# VCLFO_th.net
KiCad netlist of a schematic drawn in EAGLE
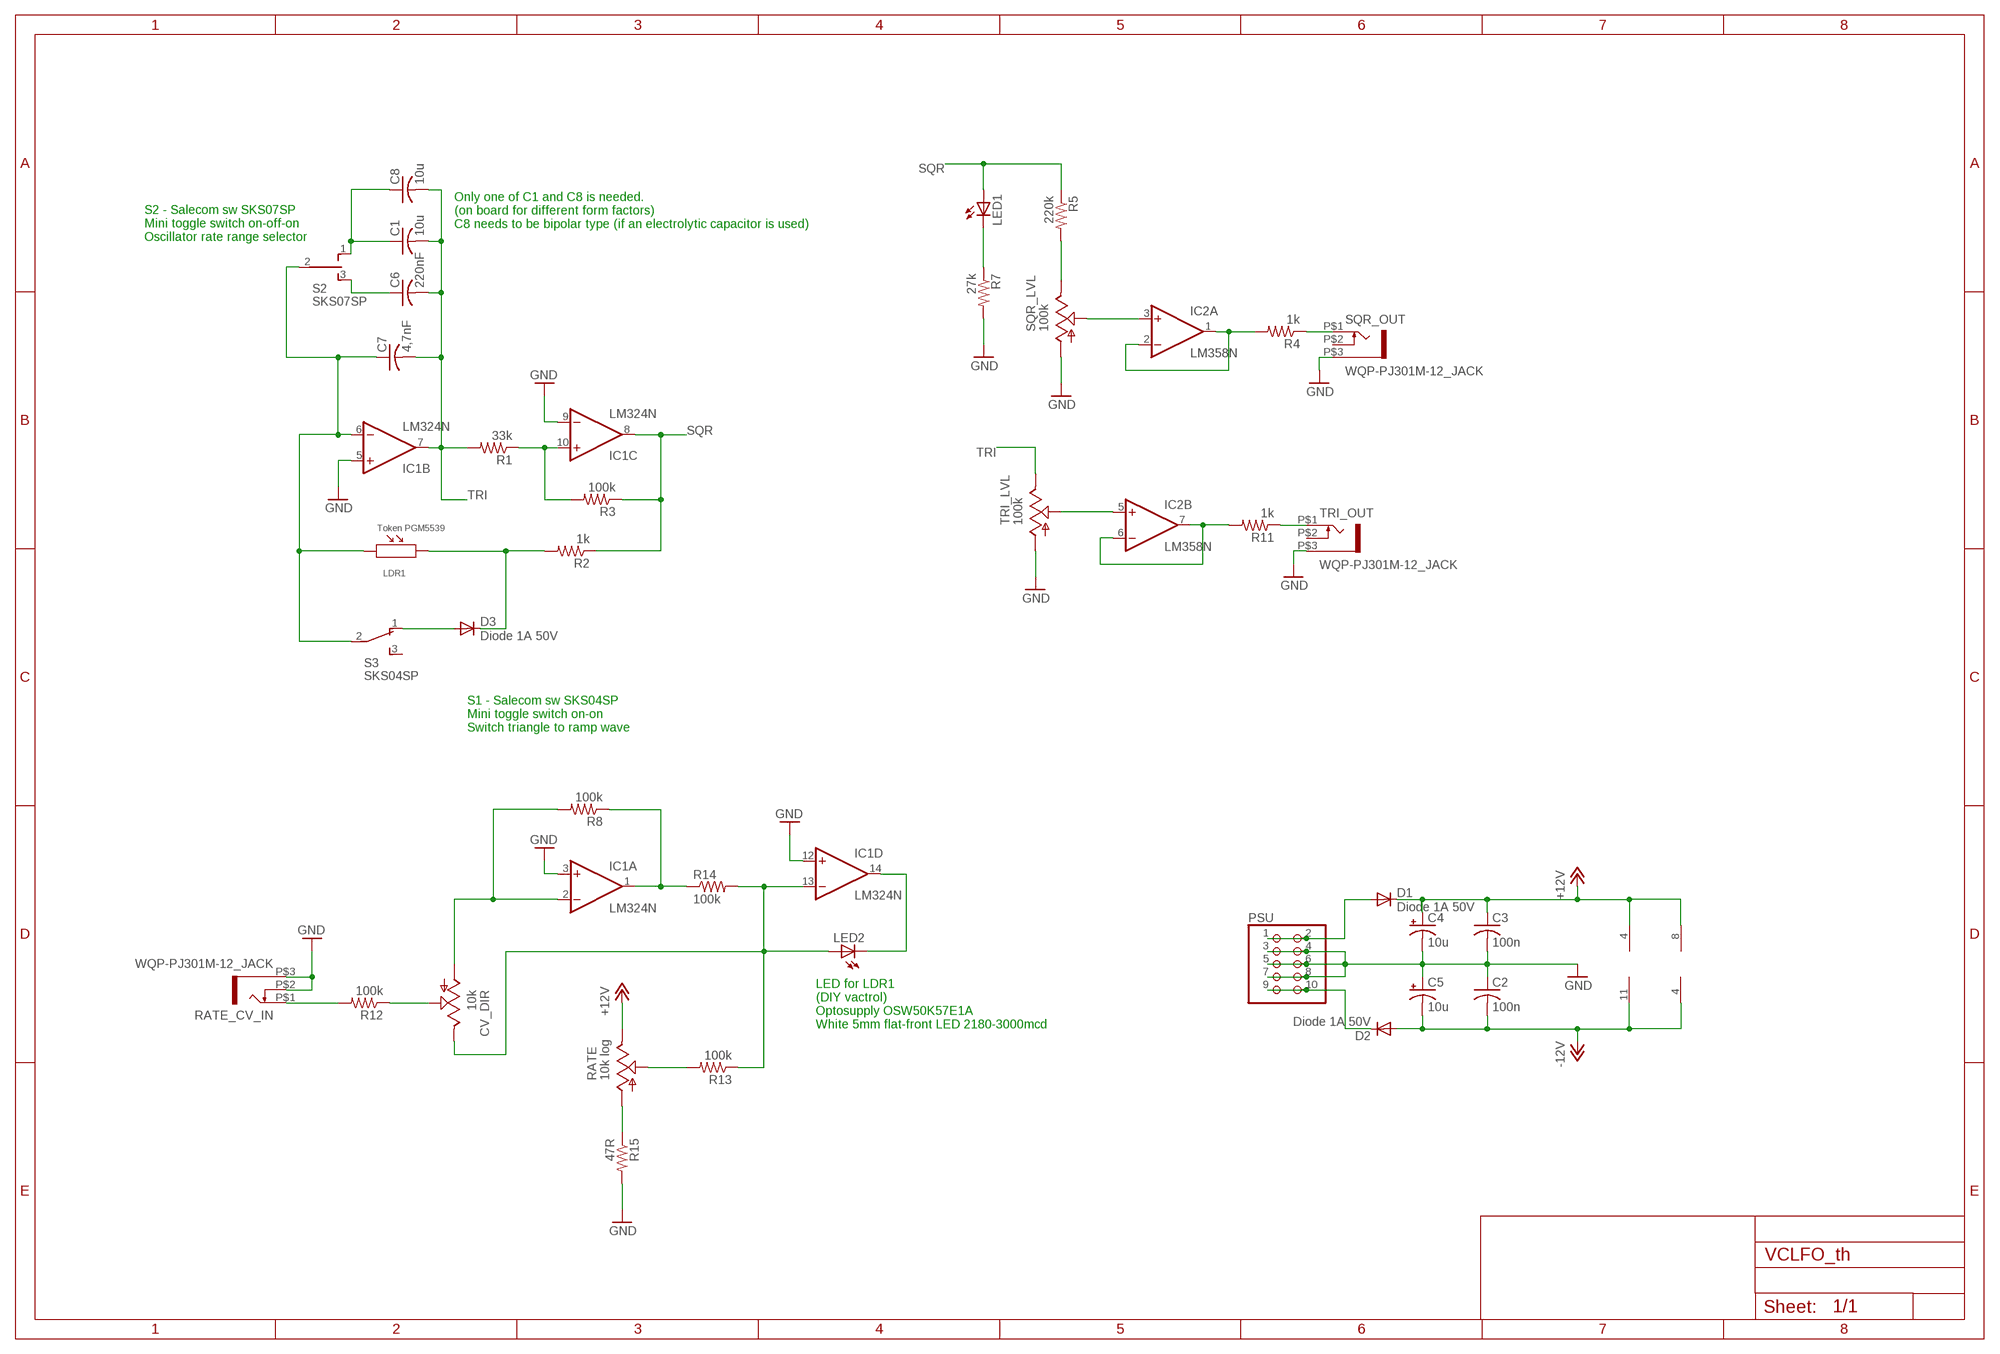
[diagram p0: schematic, sheet 1]

(export (version "E")
  (design (tool "Eeschema 10.0.6"))
  (components
    (comp (ref "C1")
      (value "10u")
      (footprint "eagle-import:C1206")
      (libsource (lib "eagle-import") (part "C-USC1206"))
    )
    (comp (ref "C2")
      (value "100n")
      (footprint "eagle-import:C025-025X050")
      (libsource (lib "eagle-import") (part "C-US025-025X050"))
    )
    (comp (ref "C3")
      (value "100n")
      (footprint "eagle-import:C025-025X050")
      (libsource (lib "eagle-import") (part "C-US025-025X050"))
    )
    (comp (ref "C4")
      (value "10u")
      (footprint "eagle-import:E2,5-6")
      (libsource (lib "eagle-import") (part "CPOL-USE2.5-6"))
    )
    (comp (ref "C5")
      (value "10u")
      (footprint "eagle-import:E2,5-6")
      (libsource (lib "eagle-import") (part "CPOL-USE2.5-6"))
    )
    (comp (ref "C6")
      (value "220nF")
      (footprint "eagle-import:C025-025X050")
      (libsource (lib "eagle-import") (part "C-US025-025X050"))
    )
    (comp (ref "C7")
      (value "4,7nF")
      (footprint "eagle-import:C025-025X050")
      (libsource (lib "eagle-import") (part "C-US025-025X050"))
    )
    (comp (ref "C8")
      (value "10u")
      (footprint "eagle-import:C025-050X050")
      (libsource (lib "eagle-import") (part "C-US025-050X050"))
    )
    (comp (ref "CV_DIR")
      (value "10k")
      (footprint "eagle-import:ALPS_POT_VERTICAL")
      (libsource (lib "eagle-import") (part "POT_USVERTICAL"))
    )
    (comp (ref "D1")
      (value "Diode 1A 50V")
      (footprint "eagle-import:D-5")
      (libsource (lib "eagle-import") (part "DIODE-D-5"))
    )
    (comp (ref "D2")
      (value "Diode 1A 50V")
      (footprint "eagle-import:D-5")
      (libsource (lib "eagle-import") (part "DIODE-D-5"))
    )
    (comp (ref "D3")
      (value "Diode 1A 50V")
      (footprint "eagle-import:D-5")
      (libsource (lib "eagle-import") (part "DIODE-D-5"))
    )
    (comp (ref "IC1")
      (value "LM324N")
      (footprint "eagle-import:DIL14")
      (libsource (lib "eagle-import") (part "LM324N"))
    )
    (comp (ref "IC2")
      (value "LM358N")
      (footprint "eagle-import:DIL08")
      (libsource (lib "eagle-import") (part "LM358N"))
    )
    (comp (ref "LDR1")
      (value "Token PGM5539")
      (footprint "eagle-import:LDR_SNR2-3.0")
      (fields (field (name "MPN") "PGM55xx"))
      (libsource (lib "eagle-import") (part "LDR_TOKEN_PGM55XX"))
    )
    (comp (ref "LED1")
      (value "LED5MM")
      (footprint "eagle-import:LED5MM")
      (libsource (lib "eagle-import") (part "LED5MM"))
    )
    (comp (ref "LED2")
      (value "LED3MM")
      (footprint "eagle-import:LED3MM")
      (libsource (lib "eagle-import") (part "LED3MM"))
    )
    (comp (ref "PSU")
      (value "PINHD-2X5")
      (footprint "eagle-import:2X05")
      (libsource (lib "eagle-import") (part "PINHD-2X5"))
    )
    (comp (ref "R1")
      (value "33k")
      (footprint "eagle-import:0207_2V")
      (libsource (lib "eagle-import") (part "R-US_0207/2V"))
    )
    (comp (ref "R2")
      (value "1k")
      (footprint "eagle-import:0207_2V")
      (libsource (lib "eagle-import") (part "R-US_0207/2V"))
    )
    (comp (ref "R3")
      (value "100k")
      (footprint "eagle-import:0207_2V")
      (libsource (lib "eagle-import") (part "R-US_0207/2V"))
    )
    (comp (ref "R4")
      (value "1k")
      (footprint "eagle-import:0207_2V")
      (libsource (lib "eagle-import") (part "R-US_0207/2V"))
    )
    (comp (ref "R5")
      (value "220k")
      (footprint "eagle-import:0207_2V")
      (libsource (lib "eagle-import") (part "R-US_0207/2V"))
    )
    (comp (ref "R7")
      (value "27k")
      (footprint "eagle-import:0207_2V")
      (libsource (lib "eagle-import") (part "R-US_0207/2V"))
    )
    (comp (ref "R8")
      (value "100k")
      (footprint "eagle-import:0207_2V")
      (libsource (lib "eagle-import") (part "R-US_0207/2V"))
    )
    (comp (ref "R11")
      (value "1k")
      (footprint "eagle-import:0207_2V")
      (libsource (lib "eagle-import") (part "R-US_0207/2V"))
    )
    (comp (ref "R12")
      (value "100k")
      (footprint "eagle-import:0207_2V")
      (libsource (lib "eagle-import") (part "R-US_0207/2V"))
    )
    (comp (ref "R13")
      (value "100k")
      (footprint "eagle-import:0207_2V")
      (libsource (lib "eagle-import") (part "R-US_0207/2V"))
    )
    (comp (ref "R14")
      (value "100k")
      (footprint "eagle-import:0207_2V")
      (libsource (lib "eagle-import") (part "R-US_0207/2V"))
    )
    (comp (ref "R15")
      (value "47R")
      (footprint "eagle-import:0207_2V")
      (libsource (lib "eagle-import") (part "R-US_0207/2V"))
    )
    (comp (ref "RATE")
      (value "10k log")
      (footprint "eagle-import:ALPS_POT_VERTICAL")
      (libsource (lib "eagle-import") (part "POT_USVERTICAL"))
    )
    (comp (ref "RATE_CV_IN")
      (value "WQP-PJ301M-12_JACK")
      (footprint "eagle-import:WQP-PJ301M-12_JACK")
      (libsource (lib "eagle-import") (part "WQP-PJ301M-12_JACK"))
    )
    (comp (ref "S2")
      (value "SKS07SP")
      (footprint "eagle-import:TL3XPO")
      (libsource (lib "eagle-import") (part "TL39PO"))
    )
    (comp (ref "S3")
      (value "SKS04SP")
      (footprint "eagle-import:TL3XPO")
      (libsource (lib "eagle-import") (part "TL36PO"))
    )
    (comp (ref "SQR_LVL")
      (value "100k")
      (footprint "eagle-import:ALPS_POT_VERTICAL")
      (libsource (lib "eagle-import") (part "POT_USVERTICAL"))
    )
    (comp (ref "SQR_OUT")
      (value "WQP-PJ301M-12_JACK")
      (footprint "eagle-import:WQP-PJ301M-12_JACK")
      (libsource (lib "eagle-import") (part "WQP-PJ301M-12_JACK"))
    )
    (comp (ref "TRI_LVL")
      (value "100k")
      (footprint "eagle-import:ALPS_POT_VERTICAL")
      (libsource (lib "eagle-import") (part "POT_USVERTICAL"))
    )
    (comp (ref "TRI_OUT")
      (value "WQP-PJ301M-12_JACK")
      (footprint "eagle-import:WQP-PJ301M-12_JACK")
      (libsource (lib "eagle-import") (part "WQP-PJ301M-12_JACK"))
    )
  )
  (nets
    (net (code "1") (name "+12V") (class "Default")
      (node (ref "C3") (pin "1") (pinfunction "1_1") (pintype "passive"))
      (node (ref "C4") (pin "+") (pinfunction "+_+") (pintype "passive"))
      (node (ref "D1") (pin "C") (pinfunction "C_C") (pintype "passive"))
      (node (ref "IC1") (pin "4") (pinfunction "V+_4") (pintype "power_in"))
      (node (ref "IC2") (pin "8") (pinfunction "V+_8") (pintype "power_in"))
      (node (ref "RATE") (pin "P$1") (pinfunction "E_P$1") (pintype "passive"))
    )
    (net (code "2") (name "-12V") (class "Default")
      (node (ref "C2") (pin "2") (pinfunction "2_2") (pintype "passive"))
      (node (ref "C5") (pin "-") (pinfunction "-_-") (pintype "passive"))
      (node (ref "D2") (pin "A") (pinfunction "A_A") (pintype "passive"))
      (node (ref "IC1") (pin "11") (pinfunction "V-_11") (pintype "power_in"))
      (node (ref "IC2") (pin "4") (pinfunction "V-_4") (pintype "power_in"))
    )
    (net (code "3") (name "/SQR") (class "Default")
      (node (ref "IC1") (pin "8") (pinfunction "OUT_8") (pintype "output"))
      (node (ref "LED1") (pin "A") (pinfunction "A_A") (pintype "passive"))
      (node (ref "R2") (pin "1") (pinfunction "1_1") (pintype "passive"))
      (node (ref "R3") (pin "1") (pinfunction "1_1") (pintype "passive"))
      (node (ref "R5") (pin "1") (pinfunction "1_1") (pintype "passive"))
    )
    (net (code "4") (name "/TRI") (class "Default")
      (node (ref "C1") (pin "2") (pinfunction "2_2") (pintype "passive"))
      (node (ref "C6") (pin "2") (pinfunction "2_2") (pintype "passive"))
      (node (ref "C7") (pin "2") (pinfunction "2_2") (pintype "passive"))
      (node (ref "C8") (pin "2") (pinfunction "2_2") (pintype "passive"))
      (node (ref "IC1") (pin "7") (pinfunction "OUT_7") (pintype "output"))
      (node (ref "R1") (pin "2") (pinfunction "2_2") (pintype "passive"))
      (node (ref "TRI_LVL") (pin "P$1") (pinfunction "E_P$1") (pintype "passive"))
    )
    (net (code "5") (name "GND") (class "Default")
      (node (ref "C2") (pin "1") (pinfunction "1_1") (pintype "passive"))
      (node (ref "C3") (pin "2") (pinfunction "2_2") (pintype "passive"))
      (node (ref "C4") (pin "-") (pinfunction "-_-") (pintype "passive"))
      (node (ref "C5") (pin "+") (pinfunction "+_+") (pintype "passive"))
      (node (ref "IC1") (pin "12") (pinfunction "+IN_12") (pintype "input"))
      (node (ref "IC1") (pin "3") (pinfunction "+IN_3") (pintype "input"))
      (node (ref "IC1") (pin "5") (pinfunction "+IN_5") (pintype "input"))
      (node (ref "IC1") (pin "9") (pinfunction "-IN_9") (pintype "input"))
      (node (ref "PSU") (pin "3") (pinfunction "3_3") (pintype "passive"))
      (node (ref "PSU") (pin "4") (pinfunction "4_4") (pintype "passive"))
      (node (ref "PSU") (pin "5") (pinfunction "5_5") (pintype "passive"))
      (node (ref "PSU") (pin "6") (pinfunction "6_6") (pintype "passive"))
      (node (ref "PSU") (pin "7") (pinfunction "7_7") (pintype "passive"))
      (node (ref "PSU") (pin "8") (pinfunction "8_8") (pintype "passive"))
      (node (ref "R15") (pin "2") (pinfunction "2_2") (pintype "passive"))
      (node (ref "R7") (pin "2") (pinfunction "2_2") (pintype "passive"))
      (node (ref "RATE_CV_IN") (pin "P$2") (pinfunction "3_P$2") (pintype "passive"))
      (node (ref "RATE_CV_IN") (pin "P$3") (pinfunction "1_P$3") (pintype "passive"))
      (node (ref "SQR_LVL") (pin "P$3") (pinfunction "A_P$3") (pintype "passive"))
      (node (ref "SQR_OUT") (pin "P$3") (pinfunction "1_P$3") (pintype "passive"))
      (node (ref "TRI_LVL") (pin "P$3") (pinfunction "A_P$3") (pintype "passive"))
      (node (ref "TRI_OUT") (pin "P$3") (pinfunction "1_P$3") (pintype "passive"))
    )
    (net (code "6") (name "Net-(CV_DIR-A)") (class "Default")
      (node (ref "CV_DIR") (pin "P$3") (pinfunction "A_P$3") (pintype "passive"))
      (node (ref "IC1") (pin "2") (pinfunction "-IN_2") (pintype "input"))
      (node (ref "R8") (pin "2") (pinfunction "2_2") (pintype "passive"))
    )
    (net (code "7") (name "Net-(CV_DIR-E)") (class "Default")
      (node (ref "CV_DIR") (pin "P$1") (pinfunction "E_P$1") (pintype "passive"))
      (node (ref "IC1") (pin "13") (pinfunction "-IN_13") (pintype "input"))
      (node (ref "LED2") (pin "A") (pinfunction "A_A") (pintype "passive"))
      (node (ref "R13") (pin "1") (pinfunction "1_1") (pintype "passive"))
      (node (ref "R14") (pin "2") (pinfunction "2_2") (pintype "passive"))
    )
    (net (code "8") (name "Net-(CV_DIR-S)") (class "Default")
      (node (ref "CV_DIR") (pin "P$2") (pinfunction "S_P$2") (pintype "passive"))
      (node (ref "R12") (pin "1") (pinfunction "1_1") (pintype "passive"))
    )
    (net (code "9") (name "Net-(D1-PadA)") (class "Default")
      (node (ref "D1") (pin "A") (pinfunction "A_A") (pintype "passive"))
      (node (ref "PSU") (pin "1") (pinfunction "1_1") (pintype "passive"))
      (node (ref "PSU") (pin "2") (pinfunction "2_2") (pintype "passive"))
    )
    (net (code "10") (name "Net-(D2-PadC)") (class "Default")
      (node (ref "D2") (pin "C") (pinfunction "C_C") (pintype "passive"))
      (node (ref "PSU") (pin "10") (pinfunction "10_10") (pintype "passive"))
      (node (ref "PSU") (pin "9") (pinfunction "9_9") (pintype "passive"))
    )
    (net (code "11") (name "Net-(IC1A-OUT)") (class "Default")
      (node (ref "IC1") (pin "1") (pinfunction "OUT_1") (pintype "output"))
      (node (ref "R14") (pin "1") (pinfunction "1_1") (pintype "passive"))
      (node (ref "R8") (pin "1") (pinfunction "1_1") (pintype "passive"))
    )
    (net (code "12") (name "Net-(IC1B--IN)") (class "Default")
      (node (ref "C7") (pin "1") (pinfunction "1_1") (pintype "passive"))
      (node (ref "IC1") (pin "6") (pinfunction "-IN_6") (pintype "input"))
      (node (ref "LDR1") (pin "1") (pinfunction "P$1_1") (pintype "bidirectional"))
      (node (ref "S2") (pin "2") (pinfunction "P_2") (pintype "passive"))
      (node (ref "S3") (pin "2") (pinfunction "P_2") (pintype "passive"))
    )
    (net (code "13") (name "Net-(IC1C-+IN)") (class "Default")
      (node (ref "IC1") (pin "10") (pinfunction "+IN_10") (pintype "input"))
      (node (ref "R1") (pin "1") (pinfunction "1_1") (pintype "passive"))
      (node (ref "R3") (pin "2") (pinfunction "2_2") (pintype "passive"))
    )
    (net (code "14") (name "Net-(IC1D-OUT)") (class "Default")
      (node (ref "IC1") (pin "14") (pinfunction "OUT_14") (pintype "output"))
      (node (ref "LED2") (pin "K") (pinfunction "C_K") (pintype "passive"))
    )
    (net (code "15") (name "Net-(IC2A-+IN)") (class "Default")
      (node (ref "IC2") (pin "3") (pinfunction "+IN_3") (pintype "input"))
      (node (ref "SQR_LVL") (pin "P$2") (pinfunction "S_P$2") (pintype "passive"))
    )
    (net (code "16") (name "Net-(IC2A--IN)") (class "Default")
      (node (ref "IC2") (pin "1") (pinfunction "OUT_1") (pintype "output"))
      (node (ref "IC2") (pin "2") (pinfunction "-IN_2") (pintype "input"))
      (node (ref "R4") (pin "2") (pinfunction "2_2") (pintype "passive"))
    )
    (net (code "17") (name "Net-(IC2B-+IN)") (class "Default")
      (node (ref "IC2") (pin "5") (pinfunction "+IN_5") (pintype "input"))
      (node (ref "TRI_LVL") (pin "P$2") (pinfunction "S_P$2") (pintype "passive"))
    )
    (net (code "18") (name "Net-(IC2B--IN)") (class "Default")
      (node (ref "IC2") (pin "6") (pinfunction "-IN_6") (pintype "input"))
      (node (ref "IC2") (pin "7") (pinfunction "OUT_7") (pintype "output"))
      (node (ref "R11") (pin "2") (pinfunction "2_2") (pintype "passive"))
    )
    (net (code "19") (name "Net-(LDR1-P$2)") (class "Default")
      (node (ref "D3") (pin "C") (pinfunction "C_C") (pintype "passive"))
      (node (ref "LDR1") (pin "2") (pinfunction "P$2_2") (pintype "bidirectional"))
      (node (ref "R2") (pin "2") (pinfunction "2_2") (pintype "passive"))
    )
    (net (code "20") (name "Net-(LED1-C)") (class "Default")
      (node (ref "LED1") (pin "K") (pinfunction "C_K") (pintype "passive"))
      (node (ref "R7") (pin "1") (pinfunction "1_1") (pintype "passive"))
    )
    (net (code "21") (name "Net-(RATE-A)") (class "Default")
      (node (ref "R15") (pin "1") (pinfunction "1_1") (pintype "passive"))
      (node (ref "RATE") (pin "P$3") (pinfunction "A_P$3") (pintype "passive"))
    )
    (net (code "22") (name "Net-(RATE-S)") (class "Default")
      (node (ref "R13") (pin "2") (pinfunction "2_2") (pintype "passive"))
      (node (ref "RATE") (pin "P$2") (pinfunction "S_P$2") (pintype "passive"))
    )
    (net (code "23") (name "Net-(RATE_CV_IN-2)") (class "Default")
      (node (ref "R12") (pin "2") (pinfunction "2_2") (pintype "passive"))
      (node (ref "RATE_CV_IN") (pin "P$1") (pinfunction "2_P$1") (pintype "passive"))
    )
    (net (code "24") (name "Net-(S2-O)") (class "Default")
      (node (ref "C1") (pin "1") (pinfunction "1_1") (pintype "passive"))
      (node (ref "C8") (pin "1") (pinfunction "1_1") (pintype "passive"))
      (node (ref "S2") (pin "1") (pinfunction "O_1") (pintype "passive"))
    )
    (net (code "25") (name "Net-(S2-S)") (class "Default")
      (node (ref "C6") (pin "1") (pinfunction "1_1") (pintype "passive"))
      (node (ref "S2") (pin "3") (pinfunction "S_3") (pintype "passive"))
    )
    (net (code "26") (name "Net-(S3-O)") (class "Default")
      (node (ref "D3") (pin "A") (pinfunction "A_A") (pintype "passive"))
      (node (ref "S3") (pin "1") (pinfunction "O_1") (pintype "passive"))
    )
    (net (code "27") (name "Net-(SQR_LVL-E)") (class "Default")
      (node (ref "R5") (pin "2") (pinfunction "2_2") (pintype "passive"))
      (node (ref "SQR_LVL") (pin "P$1") (pinfunction "E_P$1") (pintype "passive"))
    )
    (net (code "28") (name "Net-(SQR_OUT-2)") (class "Default")
      (node (ref "R4") (pin "1") (pinfunction "1_1") (pintype "passive"))
      (node (ref "SQR_OUT") (pin "P$1") (pinfunction "2_P$1") (pintype "passive"))
    )
    (net (code "29") (name "Net-(TRI_OUT-2)") (class "Default")
      (node (ref "R11") (pin "1") (pinfunction "1_1") (pintype "passive"))
      (node (ref "TRI_OUT") (pin "P$1") (pinfunction "2_P$1") (pintype "passive"))
    )
    (net (code "30") (name "unconnected-(S3-S-Pad3)") (class "Default")
      (node (ref "S3") (pin "3") (pinfunction "S_3") (pintype "passive"))
    )
    (net (code "31") (name "unconnected-(SQR_OUT-3-PadP$2)") (class "Default")
      (node (ref "SQR_OUT") (pin "P$2") (pinfunction "3_P$2") (pintype "passive"))
    )
    (net (code "32") (name "unconnected-(TRI_OUT-3-PadP$2)") (class "Default")
      (node (ref "TRI_OUT") (pin "P$2") (pinfunction "3_P$2") (pintype "passive"))
    )
  )
)
